# SDRAM_RV1126B.net
KiCad netlist of a schematic drawn in Altium Designer
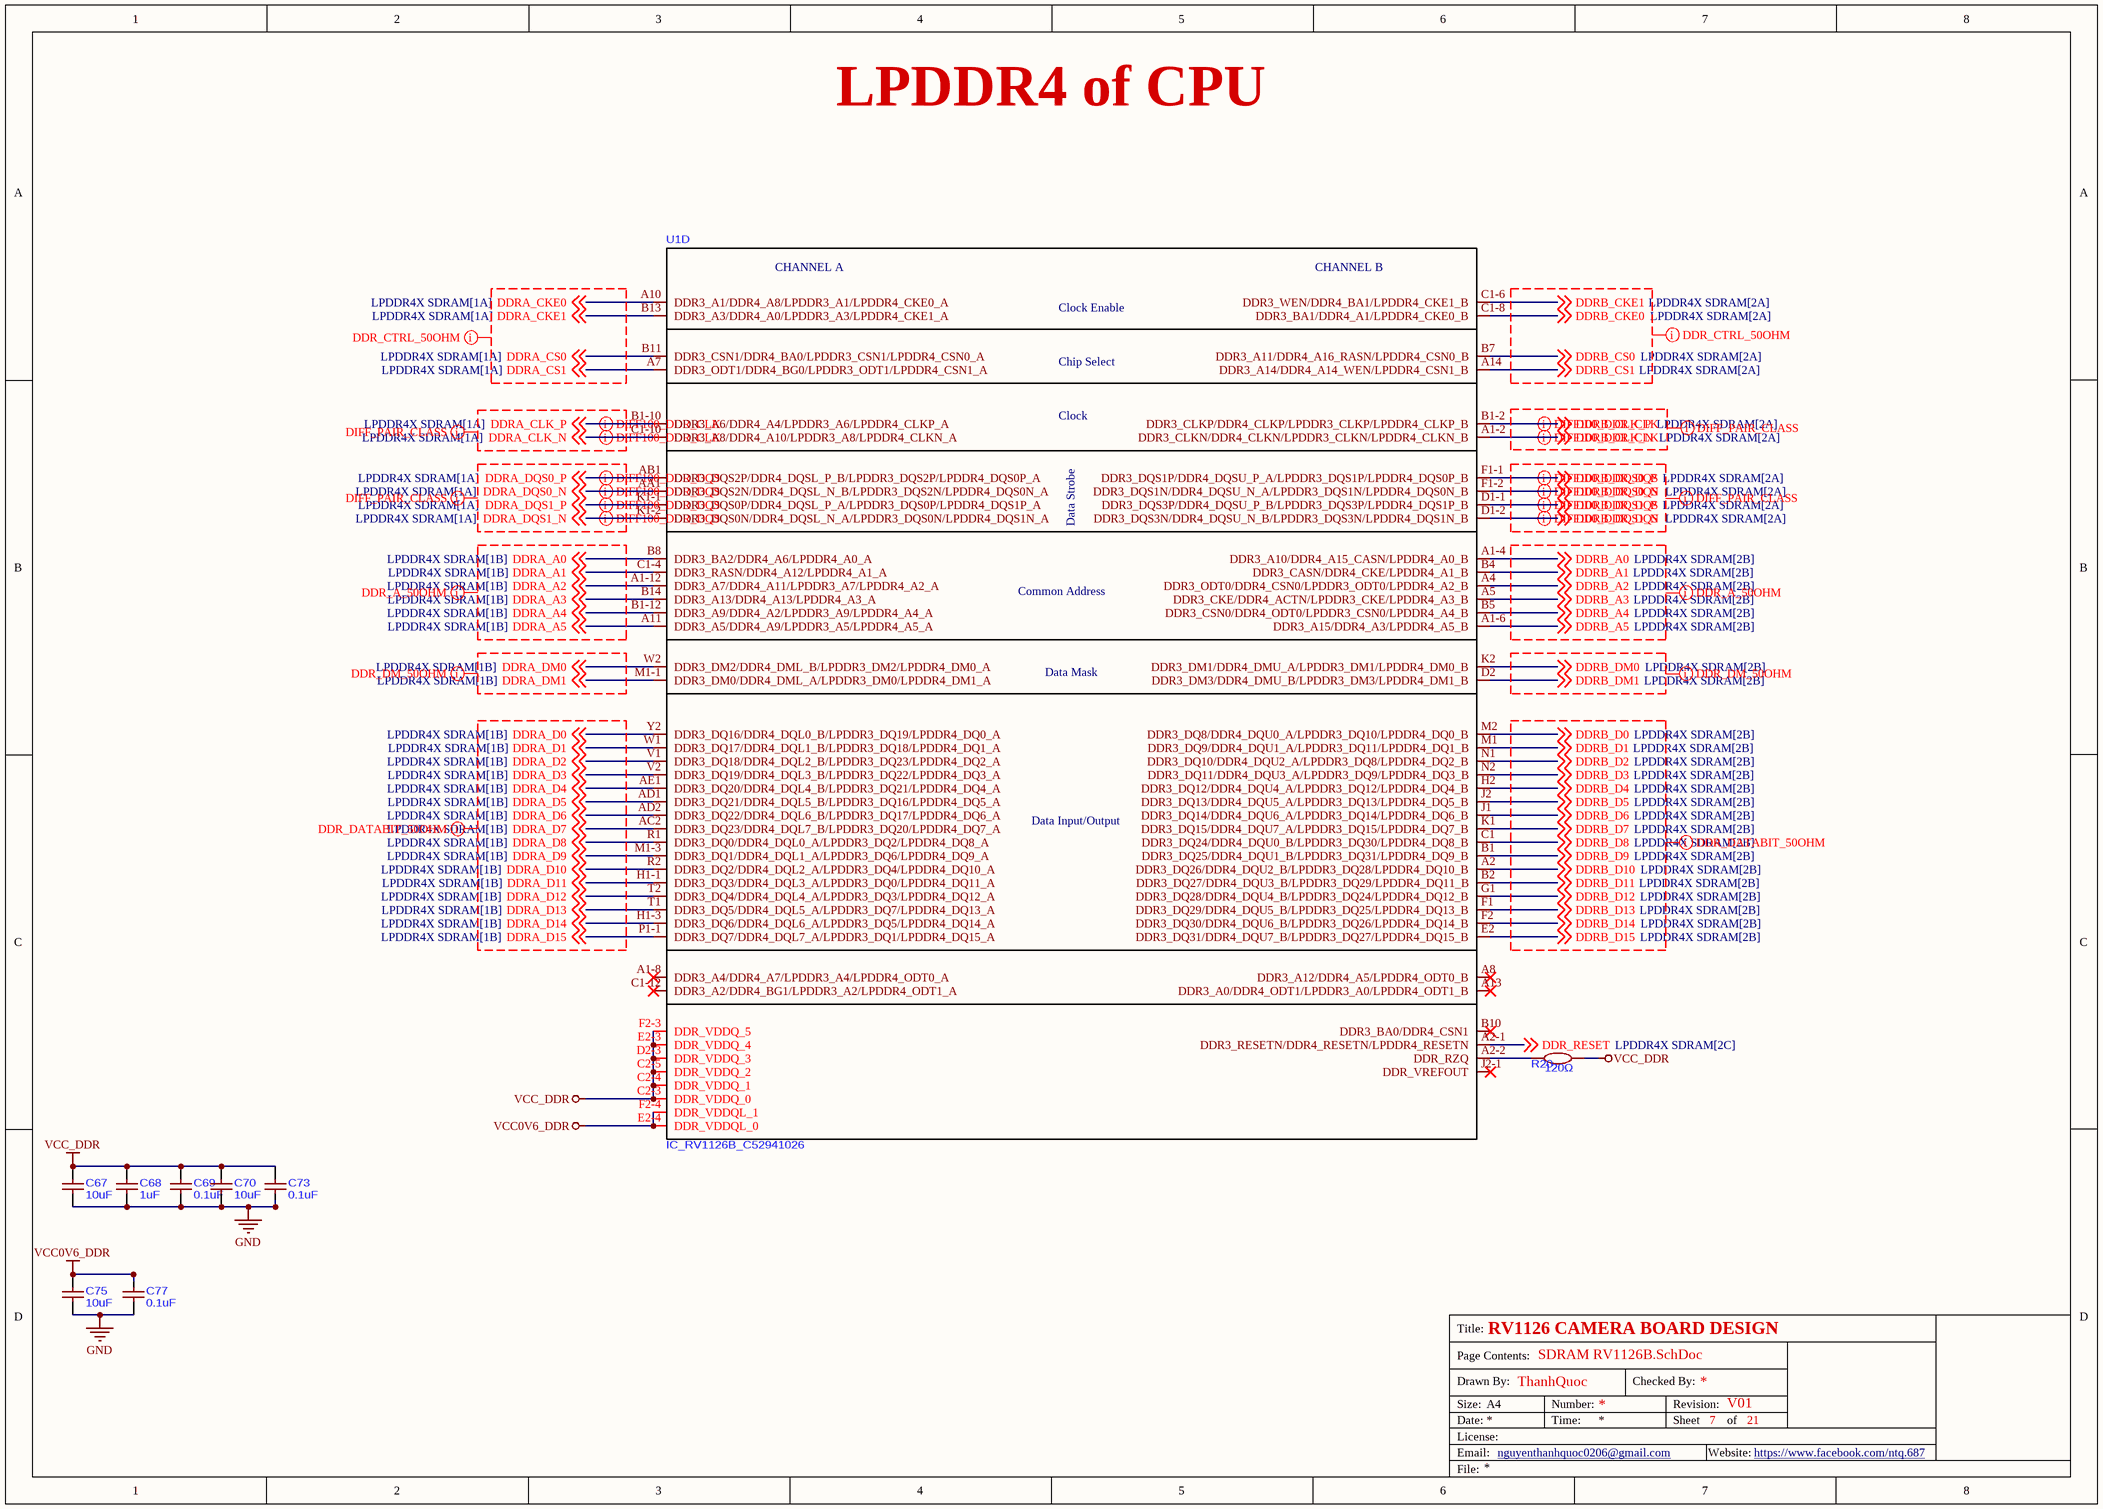
[diagram p0: SDRAM RV1126B.SchDoc]

(export (version "E")
  (design (tool "Eeschema 10.0.6"))
  (components
    (comp (ref "C67")
      (value "10uF")
      (footprint "C0402")
      (description "10µF ±20% 10V Ceramic Capacitor X5R 0402 (1005 Metric)")
      (libsource (lib "Schlib1") (part "CAP_10uF-10V-20%-0402"))
    )
    (comp (ref "C68")
      (value "1uF")
      (footprint "C0201")
      (description "1uF ±10% 6.3V Ceramic Capacitor X5R 0201")
      (libsource (lib "Schlib1") (part "CAP_1uF-6.3V-10%-0201"))
    )
    (comp (ref "C69")
      (value "0.1uF")
      (footprint "C0201")
      (description "0.1uF ±10% 6.3V Ceramic Capacitor X5R 0201")
      (libsource (lib "Schlib1") (part "CAP_100nF-6.3V-10%-0201_1"))
    )
    (comp (ref "C70")
      (value "10uF")
      (footprint "C0402")
      (description "10µF ±20% 10V Ceramic Capacitor X5R 0402 (1005 Metric)")
      (libsource (lib "Schlib1") (part "CAP_10uF-10V-20%-0402"))
    )
    (comp (ref "C73")
      (value "0.1uF")
      (footprint "C0201")
      (description "0.1uF ±10% 6.3V Ceramic Capacitor X5R 0201")
      (libsource (lib "Schlib1") (part "CAP_100nF-6.3V-10%-0201_1"))
    )
    (comp (ref "C75")
      (value "10uF")
      (footprint "C0402")
      (description "10µF ±20% 10V Ceramic Capacitor X5R 0402 (1005 Metric)")
      (libsource (lib "Schlib1") (part "CAP_10uF-10V-20%-0402"))
    )
    (comp (ref "C77")
      (value "0.1uF")
      (footprint "C0201")
      (description "0.1uF ±10% 6.3V Ceramic Capacitor X5R 0201")
      (libsource (lib "Schlib1") (part "CAP_100nF-6.3V-10%-0201_1"))
    )
    (comp (ref "R20")
      (value "120Ω")
      (footprint "R0201")
      (description "RES 120Ω ±1% 50mW 0201")
      (libsource (lib "Schlib1") (part "RES_120-50mW-1%-0201"))
    )
    (comp (ref "U1")
      (value "IC_RV1126B_C52941026")
      (footprint "CCSP-491_L14.0-W14.0-TL_RV1126B")
      (libsource (lib "Schlib1") (part "IC_RV1126B_C52941026"))
    )
  )
  (nets
    (net (code "1") (name "DDRA_A0") (class "Default")
      (node (ref "U1") (pin "B8") (pinfunction "DDR3_BA2/DDR4_A6/LPDDR4_A0_A_B8") (pintype "passive"))
    )
    (net (code "2") (name "DDRA_A1") (class "Default")
      (node (ref "U1") (pin "C1-4") (pinfunction "DDR3_RASN/DDR4_A12/LPDDR4_A1_A_C1-4") (pintype "passive"))
    )
    (net (code "3") (name "DDRA_A2") (class "Default")
      (node (ref "U1") (pin "A1-12") (pinfunction "DDR3_A7/DDR4_A11/LPDDR3_A7/LPDDR4_A2_A_A1-12") (pintype "passive"))
    )
    (net (code "4") (name "DDRA_A3") (class "Default")
      (node (ref "U1") (pin "B14") (pinfunction "DDR3_A13/DDR4_A13/LPDDR4_A3_A_B14") (pintype "passive"))
    )
    (net (code "5") (name "DDRA_A4") (class "Default")
      (node (ref "U1") (pin "B1-12") (pinfunction "DDR3_A9/DDR4_A2/LPDDR3_A9/LPDDR4_A4_A_B1-12") (pintype "passive"))
    )
    (net (code "6") (name "DDRA_A5") (class "Default")
      (node (ref "U1") (pin "A11") (pinfunction "DDR3_A5/DDR4_A9/LPDDR3_A5/LPDDR4_A5_A_A11") (pintype "passive"))
    )
    (net (code "7") (name "DDRA_CKE0") (class "Default")
      (node (ref "U1") (pin "A10") (pinfunction "DDR3_A1/DDR4_A8/LPDDR3_A1/LPDDR4_CKE0_A_A10") (pintype "passive"))
    )
    (net (code "8") (name "DDRA_CKE1") (class "Default")
      (node (ref "U1") (pin "B13") (pinfunction "DDR3_A3/DDR4_A0/LPDDR3_A3/LPDDR4_CKE1_A_B13") (pintype "passive"))
    )
    (net (code "9") (name "DDRA_CLK_N") (class "Default")
      (node (ref "U1") (pin "C1-10") (pinfunction "DDR3_A8/DDR4_A10/LPDDR3_A8/LPDDR4_CLKN_A_C1-10") (pintype "passive"))
    )
    (net (code "10") (name "DDRA_CLK_P") (class "Default")
      (node (ref "U1") (pin "B1-10") (pinfunction "DDR3_A6/DDR4_A4/LPDDR3_A6/LPDDR4_CLKP_A_B1-10") (pintype "passive"))
    )
    (net (code "11") (name "DDRA_CS0") (class "Default")
      (node (ref "U1") (pin "B11") (pinfunction "DDR3_CSN1/DDR4_BA0/LPDDR3_CSN1/LPDDR4_CSN0_A_B11") (pintype "passive"))
    )
    (net (code "12") (name "DDRA_CS1") (class "Default")
      (node (ref "U1") (pin "A7") (pinfunction "DDR3_ODT1/DDR4_BG0/LPDDR3_ODT1/LPDDR4_CSN1_A_A7") (pintype "passive"))
    )
    (net (code "13") (name "DDRA_D0") (class "Default")
      (node (ref "U1") (pin "Y2") (pinfunction "DDR3_DQ16/DDR4_DQL0_B/LPDDR3_DQ19/LPDDR4_DQ0_A_Y2") (pintype "passive"))
    )
    (net (code "14") (name "DDRA_D1") (class "Default")
      (node (ref "U1") (pin "W1") (pinfunction "DDR3_DQ17/DDR4_DQL1_B/LPDDR3_DQ18/LPDDR4_DQ1_A_W1") (pintype "passive"))
    )
    (net (code "15") (name "DDRA_D2") (class "Default")
      (node (ref "U1") (pin "V1") (pinfunction "DDR3_DQ18/DDR4_DQL2_B/LPDDR3_DQ23/LPDDR4_DQ2_A_V1") (pintype "passive"))
    )
    (net (code "16") (name "DDRA_D3") (class "Default")
      (node (ref "U1") (pin "V2") (pinfunction "DDR3_DQ19/DDR4_DQL3_B/LPDDR3_DQ22/LPDDR4_DQ3_A_V2") (pintype "passive"))
    )
    (net (code "17") (name "DDRA_D4") (class "Default")
      (node (ref "U1") (pin "AE1") (pinfunction "DDR3_DQ20/DDR4_DQL4_B/LPDDR3_DQ21/LPDDR4_DQ4_A_AE1") (pintype "passive"))
    )
    (net (code "18") (name "DDRA_D5") (class "Default")
      (node (ref "U1") (pin "AD1") (pinfunction "DDR3_DQ21/DDR4_DQL5_B/LPDDR3_DQ16/LPDDR4_DQ5_A_AD1") (pintype "passive"))
    )
    (net (code "19") (name "DDRA_D6") (class "Default")
      (node (ref "U1") (pin "AD2") (pinfunction "DDR3_DQ22/DDR4_DQL6_B/LPDDR3_DQ17/LPDDR4_DQ6_A_AD2") (pintype "passive"))
    )
    (net (code "20") (name "DDRA_D7") (class "Default")
      (node (ref "U1") (pin "AC2") (pinfunction "DDR3_DQ23/DDR4_DQL7_B/LPDDR3_DQ20/LPDDR4_DQ7_A_AC2") (pintype "passive"))
    )
    (net (code "21") (name "DDRA_D8") (class "Default")
      (node (ref "U1") (pin "R1") (pinfunction "DDR3_DQ0/DDR4_DQL0_A/LPDDR3_DQ2/LPDDR4_DQ8_A_R1") (pintype "passive"))
    )
    (net (code "22") (name "DDRA_D9") (class "Default")
      (node (ref "U1") (pin "M1-3") (pinfunction "DDR3_DQ1/DDR4_DQL1_A/LPDDR3_DQ6/LPDDR4_DQ9_A_M1-3") (pintype "passive"))
    )
    (net (code "23") (name "DDRA_D10") (class "Default")
      (node (ref "U1") (pin "R2") (pinfunction "DDR3_DQ2/DDR4_DQL2_A/LPDDR3_DQ4/LPDDR4_DQ10_A_R2") (pintype "passive"))
    )
    (net (code "24") (name "DDRA_D11") (class "Default")
      (node (ref "U1") (pin "H1-1") (pinfunction "DDR3_DQ3/DDR4_DQL3_A/LPDDR3_DQ0/LPDDR4_DQ11_A_H1-1") (pintype "passive"))
    )
    (net (code "25") (name "DDRA_D12") (class "Default")
      (node (ref "U1") (pin "T2") (pinfunction "DDR3_DQ4/DDR4_DQL4_A/LPDDR3_DQ3/LPDDR4_DQ12_A_T2") (pintype "passive"))
    )
    (net (code "26") (name "DDRA_D13") (class "Default")
      (node (ref "U1") (pin "T1") (pinfunction "DDR3_DQ5/DDR4_DQL5_A/LPDDR3_DQ7/LPDDR4_DQ13_A_T1") (pintype "passive"))
    )
    (net (code "27") (name "DDRA_D14") (class "Default")
      (node (ref "U1") (pin "H1-3") (pinfunction "DDR3_DQ6/DDR4_DQL6_A/LPDDR3_DQ5/LPDDR4_DQ14_A_H1-3") (pintype "passive"))
    )
    (net (code "28") (name "DDRA_D15") (class "Default")
      (node (ref "U1") (pin "P1-1") (pinfunction "DDR3_DQ7/DDR4_DQL7_A/LPDDR3_DQ1/LPDDR4_DQ15_A_P1-1") (pintype "passive"))
    )
    (net (code "29") (name "DDRA_DM0") (class "Default")
      (node (ref "U1") (pin "W2") (pinfunction "DDR3_DM2/DDR4_DML_B/LPDDR3_DM2/LPDDR4_DM0_A_W2") (pintype "passive"))
    )
    (net (code "30") (name "DDRA_DM1") (class "Default")
      (node (ref "U1") (pin "M1-1") (pinfunction "DDR3_DM0/DDR4_DML_A/LPDDR3_DM0/LPDDR4_DM1_A_M1-1") (pintype "passive"))
    )
    (net (code "31") (name "DDRA_DQS0_N") (class "Default")
      (node (ref "U1") (pin "AA1") (pinfunction "DDR3_DQS2N/DDR4_DQSL_N_B/LPDDR3_DQS2N/LPDDR4_DQS0N_A_AA1") (pintype "passive"))
    )
    (net (code "32") (name "DDRA_DQS0_P") (class "Default")
      (node (ref "U1") (pin "AB1") (pinfunction "DDR3_DQS2P/DDR4_DQSL_P_B/LPDDR3_DQS2P/LPDDR4_DQS0P_A_AB1") (pintype "passive"))
    )
    (net (code "33") (name "DDRA_DQS1_N") (class "Default")
      (node (ref "U1") (pin "K1-2") (pinfunction "DDR3_DQS0N/DDR4_DQSL_N_A/LPDDR3_DQS0N/LPDDR4_DQS1N_A_K1-2") (pintype "passive"))
    )
    (net (code "34") (name "DDRA_DQS1_P") (class "Default")
      (node (ref "U1") (pin "K1-1") (pinfunction "DDR3_DQS0P/DDR4_DQSL_P_A/LPDDR3_DQS0P/LPDDR4_DQS1P_A_K1-1") (pintype "passive"))
    )
    (net (code "35") (name "DDRB_A0") (class "Default")
      (node (ref "U1") (pin "A1-4") (pinfunction "DDR3_A10/DDR4_A15_CASN/LPDDR4_A0_B_A1-4") (pintype "passive"))
    )
    (net (code "36") (name "DDRB_A1") (class "Default")
      (node (ref "U1") (pin "B4") (pinfunction "DDR3_CASN/DDR4_CKE/LPDDR4_A1_B_B4") (pintype "passive"))
    )
    (net (code "37") (name "DDRB_A2") (class "Default")
      (node (ref "U1") (pin "A4") (pinfunction "DDR3_ODT0/DDR4_CSN0/LPDDR3_ODT0/LPDDR4_A2_B_A4") (pintype "passive"))
    )
    (net (code "38") (name "DDRB_A3") (class "Default")
      (node (ref "U1") (pin "A5") (pinfunction "DDR3_CKE/DDR4_ACTN/LPDDR3_CKE/LPDDR4_A3_B_A5") (pintype "passive"))
    )
    (net (code "39") (name "DDRB_A4") (class "Default")
      (node (ref "U1") (pin "B5") (pinfunction "DDR3_CSN0/DDR4_ODT0/LPDDR3_CSN0/LPDDR4_A4_B_B5") (pintype "passive"))
    )
    (net (code "40") (name "DDRB_A5") (class "Default")
      (node (ref "U1") (pin "A1-6") (pinfunction "DDR3_A15/DDR4_A3/LPDDR4_A5_B_A1-6") (pintype "passive"))
    )
    (net (code "41") (name "DDRB_CKE0") (class "Default")
      (node (ref "U1") (pin "C1-8") (pinfunction "DDR3_BA1/DDR4_A1/LPDDR4_CKE0_B_C1-8") (pintype "passive"))
    )
    (net (code "42") (name "DDRB_CKE1") (class "Default")
      (node (ref "U1") (pin "C1-6") (pinfunction "DDR3_WEN/DDR4_BA1/LPDDR4_CKE1_B_C1-6") (pintype "passive"))
    )
    (net (code "43") (name "DDRB_CLK_N") (class "Default")
      (node (ref "U1") (pin "A1-2") (pinfunction "DDR3_CLKN/DDR4_CLKN/LPDDR3_CLKN/LPDDR4_CLKN_B_A1-2") (pintype "passive"))
    )
    (net (code "44") (name "DDRB_CLK_P") (class "Default")
      (node (ref "U1") (pin "B1-2") (pinfunction "DDR3_CLKP/DDR4_CLKP/LPDDR3_CLKP/LPDDR4_CLKP_B_B1-2") (pintype "passive"))
    )
    (net (code "45") (name "DDRB_CS0") (class "Default")
      (node (ref "U1") (pin "B7") (pinfunction "DDR3_A11/DDR4_A16_RASN/LPDDR4_CSN0_B_B7") (pintype "passive"))
    )
    (net (code "46") (name "DDRB_CS1") (class "Default")
      (node (ref "U1") (pin "A14") (pinfunction "DDR3_A14/DDR4_A14_WEN/LPDDR4_CSN1_B_A14") (pintype "passive"))
    )
    (net (code "47") (name "DDRB_D0") (class "Default")
      (node (ref "U1") (pin "M2") (pinfunction "DDR3_DQ8/DDR4_DQU0_A/LPDDR3_DQ10/LPDDR4_DQ0_B_M2") (pintype "passive"))
    )
    (net (code "48") (name "DDRB_D1") (class "Default")
      (node (ref "U1") (pin "M1") (pinfunction "DDR3_DQ9/DDR4_DQU1_A/LPDDR3_DQ11/LPDDR4_DQ1_B_M1") (pintype "passive"))
    )
    (net (code "49") (name "DDRB_D2") (class "Default")
      (node (ref "U1") (pin "N1") (pinfunction "DDR3_DQ10/DDR4_DQU2_A/LPDDR3_DQ8/LPDDR4_DQ2_B_N1") (pintype "passive"))
    )
    (net (code "50") (name "DDRB_D3") (class "Default")
      (node (ref "U1") (pin "N2") (pinfunction "DDR3_DQ11/DDR4_DQU3_A/LPDDR3_DQ9/LPDDR4_DQ3_B_N2") (pintype "passive"))
    )
    (net (code "51") (name "DDRB_D4") (class "Default")
      (node (ref "U1") (pin "H2") (pinfunction "DDR3_DQ12/DDR4_DQU4_A/LPDDR3_DQ12/LPDDR4_DQ4_B_H2") (pintype "passive"))
    )
    (net (code "52") (name "DDRB_D5") (class "Default")
      (node (ref "U1") (pin "J2") (pinfunction "DDR3_DQ13/DDR4_DQU5_A/LPDDR3_DQ13/LPDDR4_DQ5_B_J2") (pintype "passive"))
    )
    (net (code "53") (name "DDRB_D6") (class "Default")
      (node (ref "U1") (pin "J1") (pinfunction "DDR3_DQ14/DDR4_DQU6_A/LPDDR3_DQ14/LPDDR4_DQ6_B_J1") (pintype "passive"))
    )
    (net (code "54") (name "DDRB_D7") (class "Default")
      (node (ref "U1") (pin "K1") (pinfunction "DDR3_DQ15/DDR4_DQU7_A/LPDDR3_DQ15/LPDDR4_DQ7_B_K1") (pintype "passive"))
    )
    (net (code "55") (name "DDRB_D8") (class "Default")
      (node (ref "U1") (pin "C1") (pinfunction "DDR3_DQ24/DDR4_DQU0_B/LPDDR3_DQ30/LPDDR4_DQ8_B_C1") (pintype "passive"))
    )
    (net (code "56") (name "DDRB_D9") (class "Default")
      (node (ref "U1") (pin "B1") (pinfunction "DDR3_DQ25/DDR4_DQU1_B/LPDDR3_DQ31/LPDDR4_DQ9_B_B1") (pintype "passive"))
    )
    (net (code "57") (name "DDRB_D10") (class "Default")
      (node (ref "U1") (pin "A2") (pinfunction "DDR3_DQ26/DDR4_DQU2_B/LPDDR3_DQ28/LPDDR4_DQ10_B_A2") (pintype "passive"))
    )
    (net (code "58") (name "DDRB_D11") (class "Default")
      (node (ref "U1") (pin "B2") (pinfunction "DDR3_DQ27/DDR4_DQU3_B/LPDDR3_DQ29/LPDDR4_DQ11_B_B2") (pintype "passive"))
    )
    (net (code "59") (name "DDRB_D12") (class "Default")
      (node (ref "U1") (pin "G1") (pinfunction "DDR3_DQ28/DDR4_DQU4_B/LPDDR3_DQ24/LPDDR4_DQ12_B_G1") (pintype "passive"))
    )
    (net (code "60") (name "DDRB_D13") (class "Default")
      (node (ref "U1") (pin "F1") (pinfunction "DDR3_DQ29/DDR4_DQU5_B/LPDDR3_DQ25/LPDDR4_DQ13_B_F1") (pintype "passive"))
    )
    (net (code "61") (name "DDRB_D14") (class "Default")
      (node (ref "U1") (pin "F2") (pinfunction "DDR3_DQ30/DDR4_DQU6_B/LPDDR3_DQ26/LPDDR4_DQ14_B_F2") (pintype "passive"))
    )
    (net (code "62") (name "DDRB_D15") (class "Default")
      (node (ref "U1") (pin "E2") (pinfunction "DDR3_DQ31/DDR4_DQU7_B/LPDDR3_DQ27/LPDDR4_DQ15_B_E2") (pintype "passive"))
    )
    (net (code "63") (name "DDRB_DM0") (class "Default")
      (node (ref "U1") (pin "K2") (pinfunction "DDR3_DM1/DDR4_DMU_A/LPDDR3_DM1/LPDDR4_DM0_B_K2") (pintype "passive"))
    )
    (net (code "64") (name "DDRB_DM1") (class "Default")
      (node (ref "U1") (pin "D2") (pinfunction "DDR3_DM3/DDR4_DMU_B/LPDDR3_DM3/LPDDR4_DM1_B_D2") (pintype "passive"))
    )
    (net (code "65") (name "DDRB_DQS0_N") (class "Default")
      (node (ref "U1") (pin "F1-2") (pinfunction "DDR3_DQS1N/DDR4_DQSU_N_A/LPDDR3_DQS1N/LPDDR4_DQS0N_B_F1-2") (pintype "passive"))
    )
    (net (code "66") (name "DDRB_DQS0_P") (class "Default")
      (node (ref "U1") (pin "F1-1") (pinfunction "DDR3_DQS1P/DDR4_DQSU_P_A/LPDDR3_DQS1P/LPDDR4_DQS0P_B_F1-1") (pintype "passive"))
    )
    (net (code "67") (name "DDRB_DQS1_N") (class "Default")
      (node (ref "U1") (pin "D1-2") (pinfunction "DDR3_DQS3N/DDR4_DQSU_N_B/LPDDR3_DQS3N/LPDDR4_DQS1N_B_D1-2") (pintype "passive"))
    )
    (net (code "68") (name "DDRB_DQS1_P") (class "Default")
      (node (ref "U1") (pin "D1-1") (pinfunction "DDR3_DQS3P/DDR4_DQSU_P_B/LPDDR3_DQS3P/LPDDR4_DQS1P_B_D1-1") (pintype "passive"))
    )
    (net (code "69") (name "DDR_RESET") (class "Default")
      (node (ref "U1") (pin "A2-1") (pinfunction "DDR3_RESETN/DDR4_RESETN/LPDDR4_RESETN_A2-1") (pintype "passive"))
    )
    (net (code "70") (name "GND") (class "Default")
      (node (ref "C67") (pin "1") (pinfunction "1_1") (pintype "passive"))
      (node (ref "C68") (pin "1") (pinfunction "1_1") (pintype "passive"))
      (node (ref "C69") (pin "1") (pinfunction "1_1") (pintype "passive"))
      (node (ref "C70") (pin "1") (pinfunction "1_1") (pintype "passive"))
      (node (ref "C73") (pin "1") (pinfunction "1_1") (pintype "passive"))
      (node (ref "C75") (pin "1") (pinfunction "1_1") (pintype "passive"))
      (node (ref "C77") (pin "1") (pinfunction "1_1") (pintype "passive"))
    )
    (net (code "71") (name "Net-(U1D-DDR_RZQ)") (class "Default")
      (node (ref "R20") (pin "2") (pinfunction "2_2") (pintype "passive"))
      (node (ref "U1") (pin "A2-2") (pinfunction "DDR_RZQ_A2-2") (pintype "passive"))
    )
    (net (code "72") (name "VCC0V6_DDR") (class "Default")
      (node (ref "C75") (pin "2") (pinfunction "2_2") (pintype "passive"))
      (node (ref "C77") (pin "2") (pinfunction "2_2") (pintype "passive"))
      (node (ref "U1") (pin "E2-4") (pinfunction "DDR_VDDQL_0_E2-4") (pintype "passive"))
      (node (ref "U1") (pin "F2-4") (pinfunction "DDR_VDDQL_1_F2-4") (pintype "passive"))
    )
    (net (code "73") (name "VCC_DDR") (class "Default")
      (node (ref "C67") (pin "2") (pinfunction "2_2") (pintype "passive"))
      (node (ref "C68") (pin "2") (pinfunction "2_2") (pintype "passive"))
      (node (ref "C69") (pin "2") (pinfunction "2_2") (pintype "passive"))
      (node (ref "C70") (pin "2") (pinfunction "2_2") (pintype "passive"))
      (node (ref "C73") (pin "2") (pinfunction "2_2") (pintype "passive"))
      (node (ref "R20") (pin "1") (pinfunction "1_1") (pintype "passive"))
      (node (ref "U1") (pin "C2-3") (pinfunction "DDR_VDDQ_0_C2-3") (pintype "passive"))
      (node (ref "U1") (pin "C2-4") (pinfunction "DDR_VDDQ_1_C2-4") (pintype "passive"))
      (node (ref "U1") (pin "C2-5") (pinfunction "DDR_VDDQ_2_C2-5") (pintype "passive"))
      (node (ref "U1") (pin "D2-3") (pinfunction "DDR_VDDQ_3_D2-3") (pintype "passive"))
      (node (ref "U1") (pin "E2-3") (pinfunction "DDR_VDDQ_4_E2-3") (pintype "passive"))
      (node (ref "U1") (pin "F2-3") (pinfunction "DDR_VDDQ_5_F2-3") (pintype "passive"))
    )
    (net (code "74") (name "unconnected-(U1D-DDR3_A0{slash}DDR4_ODT1{slash}LPDDR3_A0{slash}LPDDR4_ODT1_B-PadA13)") (class "Default")
      (node (ref "U1") (pin "A13") (pinfunction "DDR3_A0/DDR4_ODT1/LPDDR3_A0/LPDDR4_ODT1_B_A13") (pintype "passive+no_connect"))
    )
    (net (code "75") (name "unconnected-(U1D-DDR3_A2{slash}DDR4_BG1{slash}LPDDR3_A2{slash}LPDDR4_ODT1_A-PadC1-12)") (class "Default")
      (node (ref "U1") (pin "C1-12") (pinfunction "DDR3_A2/DDR4_BG1/LPDDR3_A2/LPDDR4_ODT1_A_C1-12") (pintype "passive+no_connect"))
    )
    (net (code "76") (name "unconnected-(U1D-DDR3_A4{slash}DDR4_A7{slash}LPDDR3_A4{slash}LPDDR4_ODT0_A-PadA1-8)") (class "Default")
      (node (ref "U1") (pin "A1-8") (pinfunction "DDR3_A4/DDR4_A7/LPDDR3_A4/LPDDR4_ODT0_A_A1-8") (pintype "passive+no_connect"))
    )
    (net (code "77") (name "unconnected-(U1D-DDR3_A12{slash}DDR4_A5{slash}LPDDR4_ODT0_B-PadA8)") (class "Default")
      (node (ref "U1") (pin "A8") (pinfunction "DDR3_A12/DDR4_A5/LPDDR4_ODT0_B_A8") (pintype "passive+no_connect"))
    )
    (net (code "78") (name "unconnected-(U1D-DDR3_BA0{slash}DDR4_CSN1-PadB10)") (class "Default")
      (node (ref "U1") (pin "B10") (pinfunction "DDR3_BA0/DDR4_CSN1_B10") (pintype "passive+no_connect"))
    )
    (net (code "79") (name "unconnected-(U1D-DDR_VREFOUT-PadJ2-1)") (class "Default")
      (node (ref "U1") (pin "J2-1") (pinfunction "DDR_VREFOUT_J2-1") (pintype "passive+no_connect"))
    )
  )
)
